# pihat.net
KiCad netlist of a schematic drawn in EAGLE
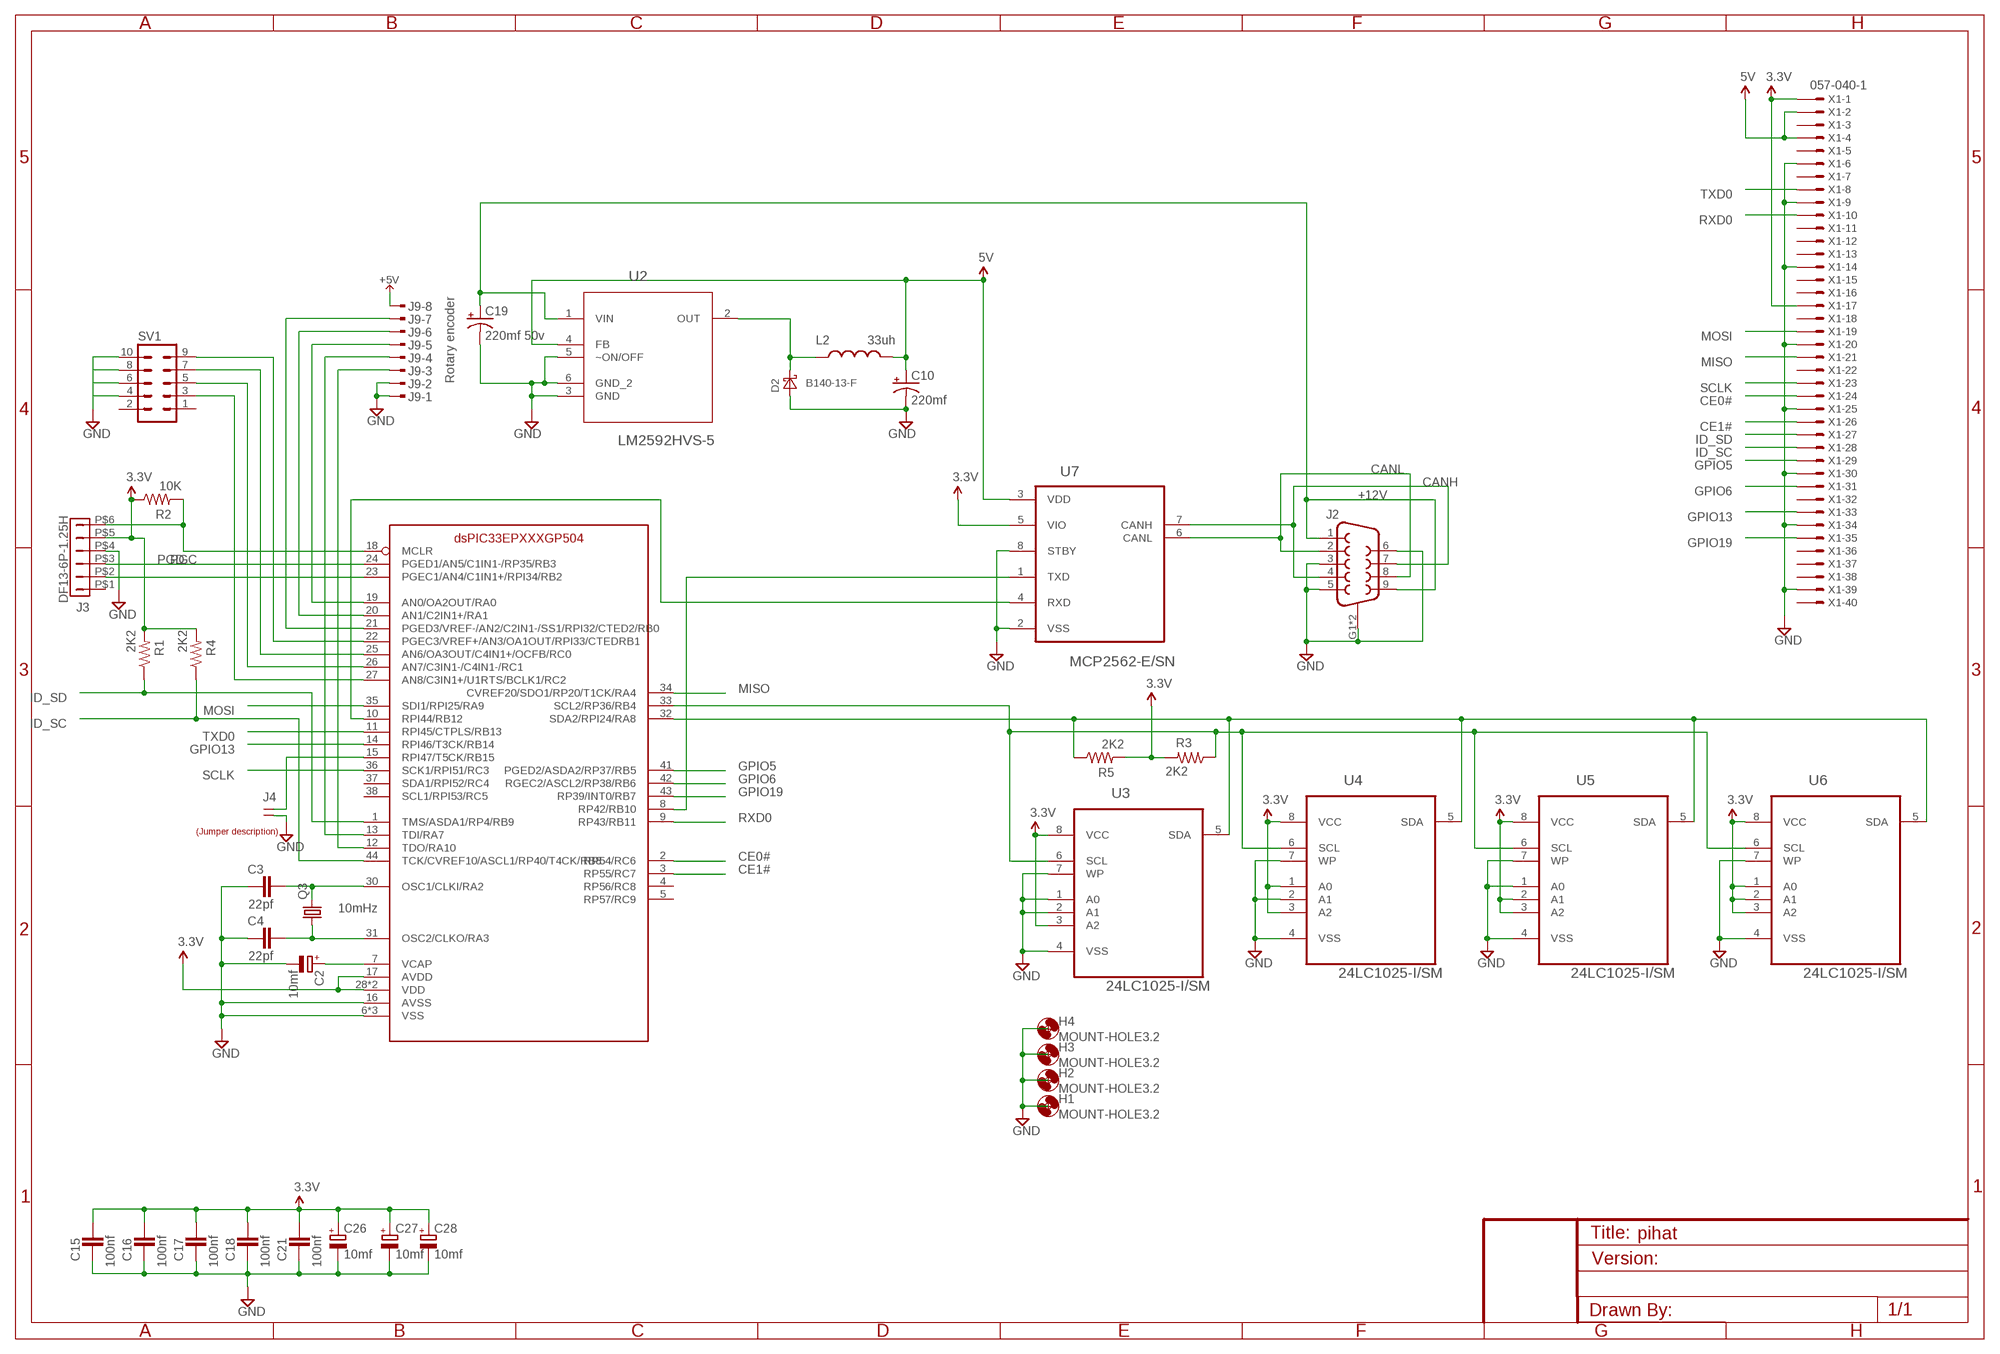
[diagram p0: schematic, sheet 1]

(export (version "E")
  (design (tool "Eeschema 10.0.6"))
  (components
    (comp (ref "C2")
      (value "10mf")
      (footprint "eagle-import:SMC_A")
      (fields (field (name "PARTNO") "T491A106K004AT"))
      (libsource (lib "eagle-import") (part "CAPACITOR_POL-SMC_A"))
    )
    (comp (ref "C3")
      (value "22pf")
      (footprint "eagle-import:C805")
      (fields (field (name "PARTNO") "C0805C220J5GACTU"))
      (libsource (lib "eagle-import") (part "CAPACITOR_NPOL-0805"))
    )
    (comp (ref "C4")
      (value "22pf")
      (footprint "eagle-import:C805")
      (fields (field (name "PARTNO") "C0805C220J5GACTU"))
      (libsource (lib "eagle-import") (part "CAPACITOR_NPOL-0805"))
    )
    (comp (ref "C10")
      (value "220mf")
      (footprint "eagle-import:EIA7343")
      (fields (field (name "PARTNO") "T545X227M016ATE035"))
      (libsource (lib "eagle-import") (part "CAP_POL7343"))
    )
    (comp (ref "C15")
      (value "100nf")
      (footprint "eagle-import:C805")
      (fields (field (name "PARTNO") "CL21F104ZBCNNNC"))
      (libsource (lib "eagle-import") (part "CAPACITOR_NPOL-0805"))
    )
    (comp (ref "C16")
      (value "100nf")
      (footprint "eagle-import:C805")
      (fields (field (name "PARTNO") "CL21F104ZBCNNNC"))
      (libsource (lib "eagle-import") (part "CAPACITOR_NPOL-0805"))
    )
    (comp (ref "C17")
      (value "100nf")
      (footprint "eagle-import:C805")
      (fields (field (name "PARTNO") "CL21F104ZBCNNNC"))
      (libsource (lib "eagle-import") (part "CAPACITOR_NPOL-0805"))
    )
    (comp (ref "C18")
      (value "100nf")
      (footprint "eagle-import:C805")
      (fields (field (name "PARTNO") "CL21F104ZBCNNNC"))
      (libsource (lib "eagle-import") (part "CAPACITOR_NPOL-0805"))
    )
    (comp (ref "C19")
      (value "220mf 50v")
      (footprint "eagle-import:EIA7343")
      (fields (field (name "PARTNO") "T545X227M016ATE035"))
      (libsource (lib "eagle-import") (part "CAP_POL7343"))
    )
    (comp (ref "C21")
      (value "100nf")
      (footprint "eagle-import:C805")
      (fields (field (name "PARTNO") "CL21F104ZBCNNNC"))
      (libsource (lib "eagle-import") (part "CAPACITOR_NPOL-0805"))
    )
    (comp (ref "C26")
      (value "10mf")
      (footprint "eagle-import:SMC_A")
      (fields (field (name "PARTNO") "T491A106K004AT"))
      (libsource (lib "eagle-import") (part "CAPACITOR_POL-SMC_A"))
    )
    (comp (ref "C27")
      (value "10mf")
      (footprint "eagle-import:SMC_A")
      (fields (field (name "PARTNO") "T491A106K004AT"))
      (libsource (lib "eagle-import") (part "CAPACITOR_POL-SMC_A"))
    )
    (comp (ref "C28")
      (value "10mf")
      (footprint "eagle-import:SMC_A")
      (fields (field (name "PARTNO") "T491A106K004AT"))
      (libsource (lib "eagle-import") (part "CAPACITOR_POL-SMC_A"))
    )
    (comp (ref "D2")
      (value "B140-13-F")
      (footprint "eagle-import:SMA")
      (libsource (lib "eagle-import") (part "DIODE-SCHOTTKY-SMA"))
    )
    (comp (ref "H1")
      (value "MOUNT-HOLE3.2")
      (footprint "eagle-import:3,2")
      (libsource (lib "eagle-import") (part "MOUNT-HOLE3.2"))
    )
    (comp (ref "H2")
      (value "MOUNT-HOLE3.2")
      (footprint "eagle-import:3,2")
      (libsource (lib "eagle-import") (part "MOUNT-HOLE3.2"))
    )
    (comp (ref "H3")
      (value "MOUNT-HOLE3.2")
      (footprint "eagle-import:3,2")
      (libsource (lib "eagle-import") (part "MOUNT-HOLE3.2"))
    )
    (comp (ref "H4")
      (value "MOUNT-HOLE3.2")
      (footprint "eagle-import:3,2")
      (libsource (lib "eagle-import") (part "MOUNT-HOLE3.2"))
    )
    (comp (ref "J2")
      (value "DB9FEMALE")
      (footprint "eagle-import:DB9")
      (fields (field (name "PARTNO") "1734354-2"))
      (libsource (lib "eagle-import") (part "DB9FEMALE"))
    )
    (comp (ref "J3")
      (value "DF13-6P-1.25H")
      (footprint "eagle-import:DF13A-6P-1.25H")
      (fields (field (name "PARTNO") "DF13A-6P-1.25H(20)"))
      (libsource (lib "eagle-import") (part "DF13-6P-1.25H"))
    )
    (comp (ref "J4")
      (value "JUMPER-1X2")
      (footprint "eagle-import:JUMPER-1X2")
      (fields (field (name "PARTNO") "M20-9770246"))
      (libsource (lib "eagle-import") (part "JUMPER-1X2"))
    )
    (comp (ref "J9")
      (value "MTOP-8")
      (footprint "eagle-import:MTOP-8")
      (fields (field (name "PARTNO") "7-215079-8"))
      (libsource (lib "eagle-import") (part "MTOP-8"))
    )
    (comp (ref "L2")
      (value "33uh")
      (footprint "eagle-import:1812")
      (fields (field (name "PARTNO") "LQH43MN330K03L"))
      (libsource (lib "eagle-import") (part "INDUCTOR"))
    )
    (comp (ref "Q3")
      (value "10mHz")
      (footprint "eagle-import:HC49_S")
      (fields (field (name "PARTNO") "ATS100B-E"))
      (libsource (lib "eagle-import") (part "CRYSTALHC49S"))
    )
    (comp (ref "R1")
      (value "2K2")
      (footprint "eagle-import:0603-RES")
      (fields (field (name "PARTNO") "RC0603FR-072K2L"))
      (libsource (lib "eagle-import") (part "RESISTOR0603-RES"))
    )
    (comp (ref "R2")
      (value "10K")
      (footprint "eagle-import:0603-RES")
      (fields (field (name "PARTNO") "RC0603FR-0710KL"))
      (libsource (lib "eagle-import") (part "RESISTOR0603-RES"))
    )
    (comp (ref "R3")
      (value "2K2")
      (footprint "eagle-import:0603-RES")
      (fields (field (name "PARTNO") "RC0603FR-072K2L"))
      (libsource (lib "eagle-import") (part "RESISTOR0603-RES"))
    )
    (comp (ref "R4")
      (value "2K2")
      (footprint "eagle-import:0603-RES")
      (fields (field (name "PARTNO") "RC0603FR-072K2L"))
      (libsource (lib "eagle-import") (part "RESISTOR0603-RES"))
    )
    (comp (ref "R5")
      (value "2K2")
      (footprint "eagle-import:0603-RES")
      (fields (field (name "PARTNO") "RC0603FR-072K2L"))
      (libsource (lib "eagle-import") (part "RESISTOR0603-RES"))
    )
    (comp (ref "SV1")
      (value "MA05-2")
      (footprint "eagle-import:MA05-2")
      (libsource (lib "eagle-import") (part "MA05-2"))
    )
    (comp (ref "U$1")
      (value "LABEL_JUMPER_1X2")
      (footprint "eagle-import:JUMP2_DESC")
      (fields (field (name "OFF") "Normal") (field (name "ON") "Reset"))
      (libsource (lib "eagle-import") (part "LABEL_JUMPER_1X2"))
    )
    (comp (ref "U1")
      (value "DSPIC33EPXXXGP504")
      (footprint "eagle-import:TQFP44")
      (fields (field (name "PARTNO") "DSPIC33EP512GP504-I/PT"))
      (libsource (lib "eagle-import") (part "DSPIC33EPXXXGP504"))
    )
    (comp (ref "U2")
      (value "LM2592HVS-5")
      (footprint "eagle-import:TO170P1435X457-5N")
      (fields (field (name "MPN") "LM2592HVS-5.0") (field (name "PARTNO") "LM2592HVSX-3.3/NOPB"))
      (libsource (lib "eagle-import") (part "LM2592HVS-5.0"))
    )
    (comp (ref "U3")
      (value "24LC1025-I/SM")
      (footprint "eagle-import:SOIC8-N_MC")
      (fields (field (name "PARTNO") "24LC1025T-I/SN"))
      (libsource (lib "eagle-import") (part "24LC1025-I/SM"))
    )
    (comp (ref "U4")
      (value "24LC1025-I/SM")
      (footprint "eagle-import:SOIC8-N_MC")
      (fields (field (name "PARTNO") "24LC1025T-I/SN"))
      (libsource (lib "eagle-import") (part "24LC1025-I/SM"))
    )
    (comp (ref "U5")
      (value "24LC1025-I/SM")
      (footprint "eagle-import:SOIC8-N_MC")
      (fields (field (name "PARTNO") "24LC1025T-I/SN"))
      (libsource (lib "eagle-import") (part "24LC1025-I/SM"))
    )
    (comp (ref "U6")
      (value "24LC1025-I/SM")
      (footprint "eagle-import:SOIC8-N_MC")
      (fields (field (name "PARTNO") "24LC1025T-I/SN"))
      (libsource (lib "eagle-import") (part "24LC1025-I/SM"))
    )
    (comp (ref "U7")
      (value "MCP2562-E/SN")
      (footprint "eagle-import:SOIC-8N")
      (libsource (lib "eagle-import") (part "MCP2562-E/SN"))
    )
    (comp (ref "X1")
      (value "057-040-1")
      (footprint "eagle-import:057-040-1")
      (libsource (lib "eagle-import") (part "057-040-1"))
    )
  )
  (nets
    (net (code "1") (name "+5V") (class "Default")
      (node (ref "J9") (pin "8") (pinfunction "1_8") (pintype "passive"))
    )
    (net (code "2") (name "/+12V") (class "Default")
      (node (ref "C19") (pin "A") (pinfunction "+_A") (pintype "passive"))
      (node (ref "J2") (pin "1") (pinfunction "1_1") (pintype "passive"))
      (node (ref "J2") (pin "9") (pinfunction "9_9") (pintype "passive"))
      (node (ref "U2") (pin "1") (pinfunction "VIN_1") (pintype "power_in"))
    )
    (net (code "3") (name "/CANH") (class "Default")
      (node (ref "J2") (pin "4") (pinfunction "4_4") (pintype "passive"))
      (node (ref "J2") (pin "7") (pinfunction "7_7") (pintype "passive"))
      (node (ref "U7") (pin "7") (pinfunction "CANH_7") (pintype "bidirectional"))
    )
    (net (code "4") (name "/CANL") (class "Default")
      (node (ref "J2") (pin "2") (pinfunction "2_2") (pintype "passive"))
      (node (ref "J2") (pin "8") (pinfunction "8_8") (pintype "passive"))
      (node (ref "U7") (pin "6") (pinfunction "CANL_6") (pintype "bidirectional"))
    )
    (net (code "5") (name "/CE0#") (class "Default")
      (node (ref "U1") (pin "2") (pinfunction "RP54/RC6_2") (pintype "bidirectional"))
      (node (ref "X1") (pin "24") (pinfunction "S_24") (pintype "passive"))
    )
    (net (code "6") (name "/CE1#") (class "Default")
      (node (ref "U1") (pin "3") (pinfunction "RP55/RC7_3") (pintype "bidirectional"))
      (node (ref "X1") (pin "26") (pinfunction "S_26") (pintype "passive"))
    )
    (net (code "7") (name "/GPIO5") (class "Default")
      (node (ref "U1") (pin "41") (pinfunction "PGED2/ASDA2/RP37/RB5_41") (pintype "bidirectional"))
      (node (ref "X1") (pin "29") (pinfunction "S_29") (pintype "passive"))
    )
    (net (code "8") (name "/GPIO6") (class "Default")
      (node (ref "U1") (pin "42") (pinfunction "RGEC2/ASCL2/RP38/RB6_42") (pintype "bidirectional"))
      (node (ref "X1") (pin "31") (pinfunction "S_31") (pintype "passive"))
    )
    (net (code "9") (name "/GPIO13") (class "Default")
      (node (ref "U1") (pin "14") (pinfunction "RPI46/T3CK/RB14_14") (pintype "bidirectional"))
      (node (ref "X1") (pin "33") (pinfunction "S_33") (pintype "passive"))
    )
    (net (code "10") (name "/GPIO19") (class "Default")
      (node (ref "U1") (pin "43") (pinfunction "RP39/INT0/RB7_43") (pintype "bidirectional"))
      (node (ref "X1") (pin "35") (pinfunction "S_35") (pintype "passive"))
    )
    (net (code "11") (name "/ID_SC") (class "Default")
      (node (ref "R4") (pin "1") (pinfunction "1_1") (pintype "passive"))
      (node (ref "U1") (pin "44") (pinfunction "TCK/CVREF10/ASCL1/RP40/T4CK/RB8_44") (pintype "bidirectional"))
      (node (ref "X1") (pin "28") (pinfunction "S_28") (pintype "passive"))
    )
    (net (code "12") (name "/ID_SD") (class "Default")
      (node (ref "R1") (pin "1") (pinfunction "1_1") (pintype "passive"))
      (node (ref "U1") (pin "1") (pinfunction "TMS/ASDA1/RP4/RB9_1") (pintype "bidirectional"))
      (node (ref "X1") (pin "27") (pinfunction "S_27") (pintype "passive"))
    )
    (net (code "13") (name "/MISO") (class "Default")
      (node (ref "U1") (pin "34") (pinfunction "CVREF20/SDO1/RP20/T1CK/RA4_34") (pintype "bidirectional"))
      (node (ref "X1") (pin "21") (pinfunction "S_21") (pintype "passive"))
    )
    (net (code "14") (name "/MOSI") (class "Default")
      (node (ref "U1") (pin "35") (pinfunction "SDI1/RPI25/RA9_35") (pintype "bidirectional"))
      (node (ref "X1") (pin "19") (pinfunction "S_19") (pintype "passive"))
    )
    (net (code "15") (name "/PGC") (class "Default")
      (node (ref "J3") (pin "P$2") (pinfunction "2_P$2") (pintype "passive"))
      (node (ref "U1") (pin "23") (pinfunction "PGEC1/AN4/C1IN1+/RPI34/RB2_23") (pintype "bidirectional"))
    )
    (net (code "16") (name "/PGD") (class "Default")
      (node (ref "J3") (pin "P$3") (pinfunction "3_P$3") (pintype "passive"))
      (node (ref "U1") (pin "24") (pinfunction "PGED1/AN5/C1IN1-/RP35/RB3_24") (pintype "bidirectional"))
    )
    (net (code "17") (name "/RXD0") (class "Default")
      (node (ref "U1") (pin "9") (pinfunction "RP43/RB11_9") (pintype "bidirectional"))
      (node (ref "X1") (pin "10") (pinfunction "S_10") (pintype "passive"))
    )
    (net (code "18") (name "/SCLK") (class "Default")
      (node (ref "U1") (pin "36") (pinfunction "SCK1/RPI51/RC3_36") (pintype "bidirectional"))
      (node (ref "X1") (pin "23") (pinfunction "S_23") (pintype "passive"))
    )
    (net (code "19") (name "/TXD0") (class "Default")
      (node (ref "U1") (pin "11") (pinfunction "RPI45/CTPLS/RB13_11") (pintype "bidirectional"))
      (node (ref "X1") (pin "8") (pinfunction "S_8") (pintype "passive"))
    )
    (net (code "20") (name "3.3V") (class "Default")
      (node (ref "C15") (pin "1") (pinfunction "1_1") (pintype "passive"))
      (node (ref "C16") (pin "1") (pinfunction "1_1") (pintype "passive"))
      (node (ref "C17") (pin "1") (pinfunction "1_1") (pintype "passive"))
      (node (ref "C18") (pin "1") (pinfunction "1_1") (pintype "passive"))
      (node (ref "C21") (pin "1") (pinfunction "1_1") (pintype "passive"))
      (node (ref "C26") (pin "+") (pinfunction "+_+") (pintype "passive"))
      (node (ref "C27") (pin "+") (pinfunction "+_+") (pintype "passive"))
      (node (ref "C28") (pin "+") (pinfunction "+_+") (pintype "passive"))
      (node (ref "J3") (pin "P$5") (pinfunction "5_P$5") (pintype "passive"))
      (node (ref "R1") (pin "2") (pinfunction "2_2") (pintype "passive"))
      (node (ref "R2") (pin "1") (pinfunction "1_1") (pintype "passive"))
      (node (ref "R3") (pin "2") (pinfunction "2_2") (pintype "passive"))
      (node (ref "R4") (pin "2") (pinfunction "2_2") (pintype "passive"))
      (node (ref "R5") (pin "2") (pinfunction "2_2") (pintype "passive"))
      (node (ref "U1") (pin "17") (pinfunction "AVDD_17") (pintype "bidirectional"))
      (node (ref "U1") (pin "28") (pinfunction "VDD_28") (pintype "bidirectional"))
      (node (ref "U1") (pin "40") (pinfunction "VDD_40") (pintype "bidirectional"))
      (node (ref "U3") (pin "3") (pinfunction "A2_3") (pintype "input"))
      (node (ref "U3") (pin "8") (pinfunction "VCC_8") (pintype "power_in"))
      (node (ref "U4") (pin "1") (pinfunction "A0_1") (pintype "input"))
      (node (ref "U4") (pin "3") (pinfunction "A2_3") (pintype "input"))
      (node (ref "U4") (pin "8") (pinfunction "VCC_8") (pintype "power_in"))
      (node (ref "U5") (pin "2") (pinfunction "A1_2") (pintype "input"))
      (node (ref "U5") (pin "3") (pinfunction "A2_3") (pintype "input"))
      (node (ref "U5") (pin "8") (pinfunction "VCC_8") (pintype "power_in"))
      (node (ref "U6") (pin "1") (pinfunction "A0_1") (pintype "input"))
      (node (ref "U6") (pin "2") (pinfunction "A1_2") (pintype "input"))
      (node (ref "U6") (pin "3") (pinfunction "A2_3") (pintype "input"))
      (node (ref "U6") (pin "8") (pinfunction "VCC_8") (pintype "power_in"))
      (node (ref "U7") (pin "5") (pinfunction "VIO_5") (pintype "power_in"))
      (node (ref "X1") (pin "1") (pinfunction "S_1") (pintype "passive"))
      (node (ref "X1") (pin "17") (pinfunction "S_17") (pintype "passive"))
    )
    (net (code "21") (name "5V") (class "Default")
      (node (ref "C10") (pin "A") (pinfunction "+_A") (pintype "passive"))
      (node (ref "L2") (pin "2") (pinfunction "2_2") (pintype "passive"))
      (node (ref "U2") (pin "4") (pinfunction "FB_4") (pintype "input"))
      (node (ref "U7") (pin "3") (pinfunction "VDD_3") (pintype "power_in"))
      (node (ref "X1") (pin "2") (pinfunction "S_2") (pintype "passive"))
      (node (ref "X1") (pin "4") (pinfunction "S_4") (pintype "passive"))
    )
    (net (code "22") (name "GND") (class "Default")
      (node (ref "C10") (pin "C") (pinfunction "-_C") (pintype "passive"))
      (node (ref "C15") (pin "2") (pinfunction "2_2") (pintype "passive"))
      (node (ref "C16") (pin "2") (pinfunction "2_2") (pintype "passive"))
      (node (ref "C17") (pin "2") (pinfunction "2_2") (pintype "passive"))
      (node (ref "C18") (pin "2") (pinfunction "2_2") (pintype "passive"))
      (node (ref "C19") (pin "C") (pinfunction "-_C") (pintype "passive"))
      (node (ref "C2") (pin "-") (pinfunction "-_-") (pintype "passive"))
      (node (ref "C21") (pin "2") (pinfunction "2_2") (pintype "passive"))
      (node (ref "C26") (pin "-") (pinfunction "-_-") (pintype "passive"))
      (node (ref "C27") (pin "-") (pinfunction "-_-") (pintype "passive"))
      (node (ref "C28") (pin "-") (pinfunction "-_-") (pintype "passive"))
      (node (ref "C3") (pin "2") (pinfunction "2_2") (pintype "passive"))
      (node (ref "C4") (pin "2") (pinfunction "2_2") (pintype "passive"))
      (node (ref "D2") (pin "A") (pinfunction "A_A") (pintype "passive"))
      (node (ref "J2") (pin "3") (pinfunction "3_3") (pintype "passive"))
      (node (ref "J2") (pin "5") (pinfunction "5_5") (pintype "passive"))
      (node (ref "J2") (pin "6") (pinfunction "6_6") (pintype "passive"))
      (node (ref "J2") (pin "G1") (pinfunction "SHIELD_G1") (pintype "power_in"))
      (node (ref "J2") (pin "G2") (pinfunction "SHIELD_G2") (pintype "power_in"))
      (node (ref "J3") (pin "P$4") (pinfunction "4_P$4") (pintype "passive"))
      (node (ref "J4") (pin "2") (pinfunction "2_2") (pintype "bidirectional"))
      (node (ref "J9") (pin "1") (pinfunction "1_1") (pintype "passive"))
      (node (ref "J9") (pin "2") (pinfunction "1_2") (pintype "passive"))
      (node (ref "SV1") (pin "10") (pinfunction "10_10") (pintype "passive"))
      (node (ref "SV1") (pin "4") (pinfunction "4_4") (pintype "passive"))
      (node (ref "SV1") (pin "6") (pinfunction "6_6") (pintype "passive"))
      (node (ref "SV1") (pin "8") (pinfunction "8_8") (pintype "passive"))
      (node (ref "U1") (pin "16") (pinfunction "AVSS_16") (pintype "bidirectional"))
      (node (ref "U1") (pin "29") (pinfunction "VSS_29") (pintype "bidirectional"))
      (node (ref "U1") (pin "39") (pinfunction "VSS_39") (pintype "bidirectional"))
      (node (ref "U1") (pin "6") (pinfunction "VSS_6") (pintype "bidirectional"))
      (node (ref "U2") (pin "3") (pinfunction "GND_3") (pintype "passive"))
      (node (ref "U2") (pin "5") (pinfunction "~{ON/OFF}_5") (pintype "input"))
      (node (ref "U2") (pin "6") (pinfunction "GND_2_6") (pintype "passive"))
      (node (ref "U3") (pin "1") (pinfunction "A0_1") (pintype "input"))
      (node (ref "U3") (pin "2") (pinfunction "A1_2") (pintype "input"))
      (node (ref "U3") (pin "4") (pinfunction "VSS_4") (pintype "passive"))
      (node (ref "U3") (pin "7") (pinfunction "WP_7") (pintype "input"))
      (node (ref "U4") (pin "2") (pinfunction "A1_2") (pintype "input"))
      (node (ref "U4") (pin "4") (pinfunction "VSS_4") (pintype "passive"))
      (node (ref "U4") (pin "7") (pinfunction "WP_7") (pintype "input"))
      (node (ref "U5") (pin "1") (pinfunction "A0_1") (pintype "input"))
      (node (ref "U5") (pin "4") (pinfunction "VSS_4") (pintype "passive"))
      (node (ref "U5") (pin "7") (pinfunction "WP_7") (pintype "input"))
      (node (ref "U6") (pin "4") (pinfunction "VSS_4") (pintype "passive"))
      (node (ref "U6") (pin "7") (pinfunction "WP_7") (pintype "input"))
      (node (ref "U7") (pin "2") (pinfunction "VSS_2") (pintype "power_in"))
      (node (ref "U7") (pin "8") (pinfunction "STBY_8") (pintype "input"))
      (node (ref "X1") (pin "14") (pinfunction "S_14") (pintype "passive"))
      (node (ref "X1") (pin "20") (pinfunction "S_20") (pintype "passive"))
      (node (ref "X1") (pin "25") (pinfunction "S_25") (pintype "passive"))
      (node (ref "X1") (pin "30") (pinfunction "S_30") (pintype "passive"))
      (node (ref "X1") (pin "34") (pinfunction "S_34") (pintype "passive"))
      (node (ref "X1") (pin "39") (pinfunction "S_39") (pintype "passive"))
      (node (ref "X1") (pin "6") (pinfunction "S_6") (pintype "passive"))
      (node (ref "X1") (pin "9") (pinfunction "S_9") (pintype "passive"))
    )
    (net (code "23") (name "Net-(J3-6)") (class "Default")
      (node (ref "J3") (pin "P$6") (pinfunction "6_P$6") (pintype "passive"))
      (node (ref "R2") (pin "2") (pinfunction "2_2") (pintype "passive"))
      (node (ref "U1") (pin "18") (pinfunction "MCLR_18") (pintype "input"))
    )
    (net (code "24") (name "Net-(J9C-1)") (class "Default")
      (node (ref "J9") (pin "3") (pinfunction "1_3") (pintype "passive"))
      (node (ref "U1") (pin "12") (pinfunction "TDO/RA10_12") (pintype "bidirectional"))
    )
    (net (code "25") (name "Net-(J9D-1)") (class "Default")
      (node (ref "J9") (pin "4") (pinfunction "1_4") (pintype "passive"))
      (node (ref "U1") (pin "13") (pinfunction "TDI/RA7_13") (pintype "bidirectional"))
    )
    (net (code "26") (name "Net-(J9E-1)") (class "Default")
      (node (ref "J9") (pin "5") (pinfunction "1_5") (pintype "passive"))
      (node (ref "U1") (pin "19") (pinfunction "AN0/OA2OUT/RA0_19") (pintype "bidirectional"))
    )
    (net (code "27") (name "Net-(J9F-1)") (class "Default")
      (node (ref "J9") (pin "6") (pinfunction "1_6") (pintype "passive"))
      (node (ref "U1") (pin "20") (pinfunction "AN1/C2IN1+/RA1_20") (pintype "bidirectional"))
    )
    (net (code "28") (name "Net-(J9G-1)") (class "Default")
      (node (ref "J9") (pin "7") (pinfunction "1_7") (pintype "passive"))
      (node (ref "U1") (pin "21") (pinfunction "PGED3/VREF-/AN2/C2IN1-/SS1/RPI32/CTED2/RB0_21") (pintype "bidirectional"))
    )
    (net (code "29") (name "Net-(U1-AN6{slash}OA3OUT{slash}C4IN1+{slash}OCFB{slash}RC0)") (class "Default")
      (node (ref "SV1") (pin "7") (pinfunction "7_7") (pintype "passive"))
      (node (ref "U1") (pin "25") (pinfunction "AN6/OA3OUT/C4IN1+/OCFB/RC0_25") (pintype "bidirectional"))
    )
    (net (code "30") (name "Net-(U1-AN7{slash}C3IN1-{slash}C4IN1-{slash}RC1)") (class "Default")
      (node (ref "SV1") (pin "5") (pinfunction "5_5") (pintype "passive"))
      (node (ref "U1") (pin "26") (pinfunction "AN7/C3IN1-/C4IN1-/RC1_26") (pintype "bidirectional"))
    )
    (net (code "31") (name "Net-(U1-AN8{slash}C3IN1+{slash}U1RTS{slash}BCLK1{slash}RC2)") (class "Default")
      (node (ref "SV1") (pin "3") (pinfunction "3_3") (pintype "passive"))
      (node (ref "U1") (pin "27") (pinfunction "AN8/C3IN1+/U1RTS/BCLK1/RC2_27") (pintype "bidirectional"))
    )
    (net (code "32") (name "Net-(U1-OSC1{slash}CLKI{slash}RA2)") (class "Default")
      (node (ref "C3") (pin "1") (pinfunction "1_1") (pintype "passive"))
      (node (ref "Q3") (pin "2") (pinfunction "2_2") (pintype "passive"))
      (node (ref "U1") (pin "30") (pinfunction "OSC1/CLKI/RA2_30") (pintype "bidirectional"))
    )
    (net (code "33") (name "Net-(U1-OSC2{slash}CLKO{slash}RA3)") (class "Default")
      (node (ref "C4") (pin "1") (pinfunction "1_1") (pintype "passive"))
      (node (ref "Q3") (pin "1") (pinfunction "1_1") (pintype "passive"))
      (node (ref "U1") (pin "31") (pinfunction "OSC2/CLKO/RA3_31") (pintype "bidirectional"))
    )
    (net (code "34") (name "Net-(U1-PGEC3{slash}VREF+{slash}AN3{slash}OA1OUT{slash}RPI33{slash}CTEDRB1)") (class "Default")
      (node (ref "SV1") (pin "9") (pinfunction "9_9") (pintype "passive"))
      (node (ref "U1") (pin "22") (pinfunction "PGEC3/VREF+/AN3/OA1OUT/RPI33/CTEDRB1_22") (pintype "bidirectional"))
    )
    (net (code "35") (name "Net-(U1-RP42{slash}RB10)") (class "Default")
      (node (ref "U1") (pin "8") (pinfunction "RP42/RB10_8") (pintype "bidirectional"))
      (node (ref "U7") (pin "1") (pinfunction "TXD_1") (pintype "input"))
    )
    (net (code "36") (name "Net-(U1-RPI44{slash}RB12)") (class "Default")
      (node (ref "U1") (pin "10") (pinfunction "RPI44/RB12_10") (pintype "bidirectional"))
      (node (ref "U7") (pin "4") (pinfunction "RXD_4") (pintype "output"))
    )
    (net (code "37") (name "Net-(U1-RPI47{slash}T5CK{slash}RB15)") (class "Default")
      (node (ref "J4") (pin "1") (pinfunction "1_1") (pintype "bidirectional"))
      (node (ref "U1") (pin "15") (pinfunction "RPI47/T5CK/RB15_15") (pintype "bidirectional"))
    )
    (net (code "38") (name "Net-(U1-SCL2{slash}RP36{slash}RB4)") (class "Default")
      (node (ref "R3") (pin "1") (pinfunction "1_1") (pintype "passive"))
      (node (ref "U1") (pin "33") (pinfunction "SCL2/RP36/RB4_33") (pintype "bidirectional"))
      (node (ref "U3") (pin "6") (pinfunction "SCL_6") (pintype "input"))
      (node (ref "U4") (pin "6") (pinfunction "SCL_6") (pintype "input"))
      (node (ref "U5") (pin "6") (pinfunction "SCL_6") (pintype "input"))
      (node (ref "U6") (pin "6") (pinfunction "SCL_6") (pintype "input"))
    )
    (net (code "39") (name "Net-(U1-SDA2{slash}RPI24{slash}RA8)") (class "Default")
      (node (ref "R5") (pin "1") (pinfunction "1_1") (pintype "passive"))
      (node (ref "U1") (pin "32") (pinfunction "SDA2/RPI24/RA8_32") (pintype "bidirectional"))
      (node (ref "U3") (pin "5") (pinfunction "SDA_5") (pintype "bidirectional"))
      (node (ref "U4") (pin "5") (pinfunction "SDA_5") (pintype "bidirectional"))
      (node (ref "U5") (pin "5") (pinfunction "SDA_5") (pintype "bidirectional"))
      (node (ref "U6") (pin "5") (pinfunction "SDA_5") (pintype "bidirectional"))
    )
    (net (code "40") (name "Net-(U1-VCAP)") (class "Default")
      (node (ref "C2") (pin "+") (pinfunction "+_+") (pintype "passive"))
      (node (ref "U1") (pin "7") (pinfunction "VCAP_7") (pintype "bidirectional"))
    )
    (net (code "41") (name "Net-(U2-OUT)") (class "Default")
      (node (ref "D2") (pin "C") (pinfunction "C_C") (pintype "passive"))
      (node (ref "L2") (pin "1") (pinfunction "1_1") (pintype "passive"))
      (node (ref "U2") (pin "2") (pinfunction "OUT_2") (pintype "output"))
    )
    (net (code "42") (name "unconnected-(J3-1-PadP$1)") (class "Default")
      (node (ref "J3") (pin "P$1") (pinfunction "1_P$1") (pintype "passive"))
    )
    (net (code "43") (name "unconnected-(SV1-Pad1)") (class "Default")
      (node (ref "SV1") (pin "1") (pinfunction "1_1") (pintype "passive"))
    )
    (net (code "44") (name "unconnected-(SV1-Pad2)") (class "Default")
      (node (ref "SV1") (pin "2") (pinfunction "2_2") (pintype "passive"))
    )
    (net (code "45") (name "unconnected-(U1-RP56{slash}RC8-Pad4)") (class "Default")
      (node (ref "U1") (pin "4") (pinfunction "RP56/RC8_4") (pintype "bidirectional"))
    )
    (net (code "46") (name "unconnected-(U1-RP57{slash}RC9-Pad5)") (class "Default")
      (node (ref "U1") (pin "5") (pinfunction "RP57/RC9_5") (pintype "bidirectional"))
    )
    (net (code "47") (name "unconnected-(U1-SCL1{slash}RPI53{slash}RC5-Pad38)") (class "Default")
      (node (ref "U1") (pin "38") (pinfunction "SCL1/RPI53/RC5_38") (pintype "bidirectional"))
    )
    (net (code "48") (name "unconnected-(U1-SDA1{slash}RPI52{slash}RC4-Pad37)") (class "Default")
      (node (ref "U1") (pin "37") (pinfunction "SDA1/RPI52/RC4_37") (pintype "bidirectional"))
    )
    (net (code "49") (name "unconnected-(X1AD-S-Pad36)") (class "Default")
      (node (ref "X1") (pin "36") (pinfunction "S_36") (pintype "passive"))
    )
    (net (code "50") (name "unconnected-(X1AE-S-Pad37)") (class "Default")
      (node (ref "X1") (pin "37") (pinfunction "S_37") (pintype "passive"))
    )
    (net (code "51") (name "unconnected-(X1AF-S-Pad38)") (class "Default")
      (node (ref "X1") (pin "38") (pinfunction "S_38") (pintype "passive"))
    )
    (net (code "52") (name "unconnected-(X1AI-S-Pad40)") (class "Default")
      (node (ref "X1") (pin "40") (pinfunction "S_40") (pintype "passive"))
    )
    (net (code "53") (name "unconnected-(X1AJ-S-Pad5)") (class "Default")
      (node (ref "X1") (pin "5") (pinfunction "S_5") (pintype "passive"))
    )
    (net (code "54") (name "unconnected-(X1AL-S-Pad7)") (class "Default")
      (node (ref "X1") (pin "7") (pinfunction "S_7") (pintype "passive"))
    )
    (net (code "55") (name "unconnected-(X1C-S-Pad11)") (class "Default")
      (node (ref "X1") (pin "11") (pinfunction "S_11") (pintype "passive"))
    )
    (net (code "56") (name "unconnected-(X1D-S-Pad12)") (class "Default")
      (node (ref "X1") (pin "12") (pinfunction "S_12") (pintype "passive"))
    )
    (net (code "57") (name "unconnected-(X1E-S-Pad13)") (class "Default")
      (node (ref "X1") (pin "13") (pinfunction "S_13") (pintype "passive"))
    )
    (net (code "58") (name "unconnected-(X1G-S-Pad15)") (class "Default")
      (node (ref "X1") (pin "15") (pinfunction "S_15") (pintype "passive"))
    )
    (net (code "59") (name "unconnected-(X1H-S-Pad16)") (class "Default")
      (node (ref "X1") (pin "16") (pinfunction "S_16") (pintype "passive"))
    )
    (net (code "60") (name "unconnected-(X1J-S-Pad18)") (class "Default")
      (node (ref "X1") (pin "18") (pinfunction "S_18") (pintype "passive"))
    )
    (net (code "61") (name "unconnected-(X1O-S-Pad22)") (class "Default")
      (node (ref "X1") (pin "22") (pinfunction "S_22") (pintype "passive"))
    )
    (net (code "62") (name "unconnected-(X1W-S-Pad3)") (class "Default")
      (node (ref "X1") (pin "3") (pinfunction "S_3") (pintype "passive"))
    )
    (net (code "63") (name "unconnected-(X1Z-S-Pad32)") (class "Default")
      (node (ref "X1") (pin "32") (pinfunction "S_32") (pintype "passive"))
    )
  )
)
